# 12V_5V_LDO.net
KiCad netlist of a schematic drawn in Altium Designer
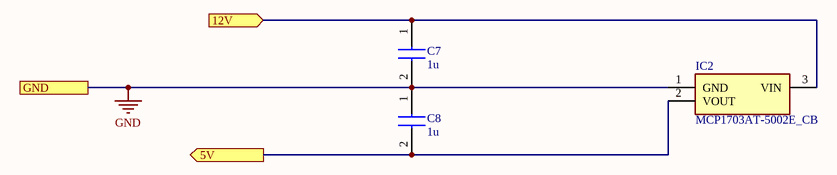
[diagram p0: 12V_5V_LDO.SchDoc]

(export (version "E")
  (design (tool "Eeschema 10.0.6"))
  (components
    (comp (ref "C7")
      (value "1u")
      (footprint "SamacSys:CAPC2012X145N")
      (description "Capacitor")
      (fields (field (name "MANUFACTURER_PART_NUMBER") "KGM21AV51H105ZU"))
      (libsource (lib "SamacSys") (part "KGM21AV51H105ZU"))
    )
    (comp (ref "C8")
      (value "1u")
      (footprint "SamacSys:CAPC2012X145N")
      (description "Capacitor")
      (fields (field (name "MANUFACTURER_PART_NUMBER") "KGM21AV51H105ZU"))
      (libsource (lib "SamacSys") (part "KGM21AV51H105ZU"))
    )
    (comp (ref "IC2")
      (value "MCP1703AT-5002E_CB")
      (footprint "SamacSys:SOT95P255X145-3N")
      (description "Integrated Circuit")
      (fields
        (field (name "MANUFACTURER_PART_NUMBER") "MCP1703AT-5002E/CB")
        (field (name "MOUSER PART NUMBER") "579-MCP1703AT5002ECB")
      )
      (libsource (lib "SamacSys") (part "MCP1703AT-5002E_CB"))
    )
  )
  (nets
    (net (code "1") (name "/5V") (class "Default")
      (node (ref "C8") (pin "2") (pinfunction "2_2") (pintype "passive"))
      (node (ref "IC2") (pin "2") (pinfunction "VOUT_2") (pintype "passive"))
    )
    (net (code "2") (name "/12V") (class "Default")
      (node (ref "C7") (pin "1") (pinfunction "1_1") (pintype "passive"))
      (node (ref "IC2") (pin "3") (pinfunction "VIN_3") (pintype "passive"))
    )
    (net (code "3") (name "GND") (class "Default")
      (node (ref "C7") (pin "2") (pinfunction "2_2") (pintype "passive"))
      (node (ref "C8") (pin "1") (pinfunction "1_1") (pintype "passive"))
      (node (ref "IC2") (pin "1") (pinfunction "GND_1") (pintype "passive"))
    )
  )
)
